# JY01.net
KiCad netlist of a schematic drawn in Altium Designer
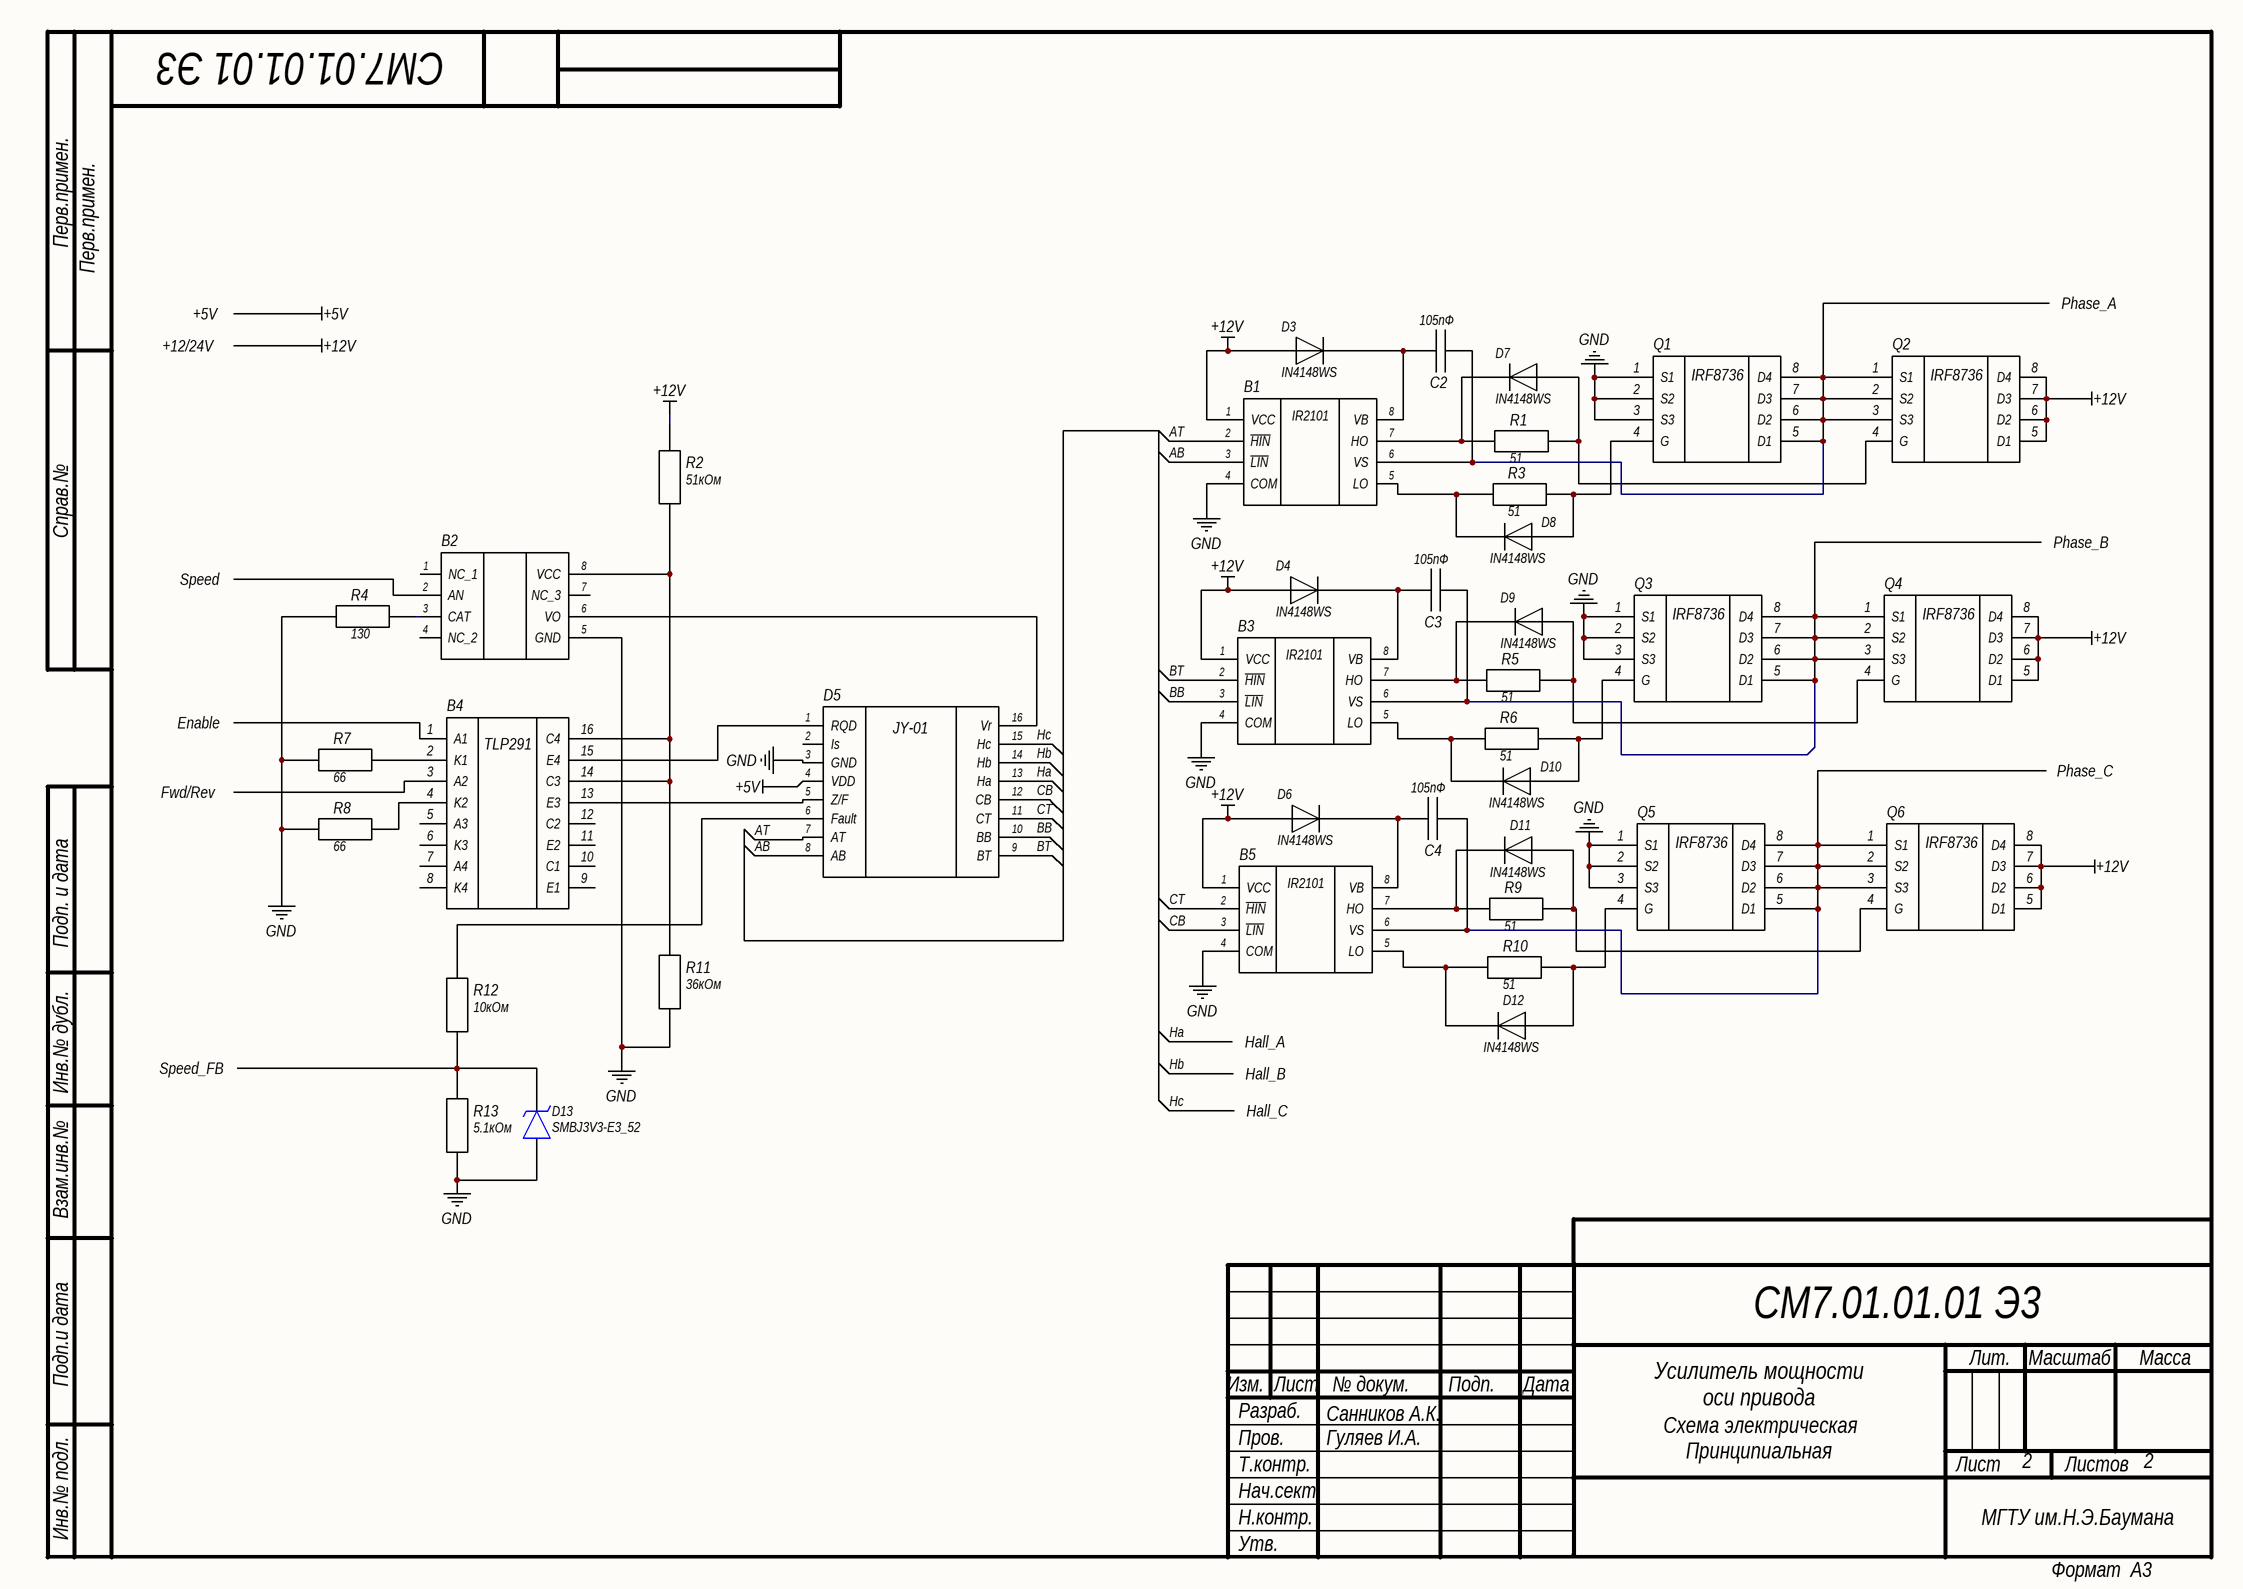
[diagram p0: Схема_принципиальная_JY01.SchDoc]

(export (version "E")
  (design (tool "Eeschema 10.0.6"))
  (components
    (comp (ref "B1")
      (value "IR2101S")
      (footprint "SOIC127P600X175-8N")
      (description "IC GATE DRVR HALF-BRIDGE 8SOIC")
      (libsource (lib "BLDC_Library") (part "IR2101S"))
    )
    (comp (ref "B2")
      (value "HCPL-4504-000E")
      (footprint "DIP762W65P254L965H470Q8N")
      (description "Optocoupler, Transistor Output, 1 Channel, DIP, 8 Pins, 25 mA, 3.75 kV, 25 %")
      (fields (field (name "MOUSER PART NUMBER") "630-HCPL-4504-000E"))
      (libsource (lib "BLDC_Library") (part "HCPL-4504-000E"))
    )
    (comp (ref "B3")
      (value "IR2101S")
      (footprint "SOIC127P600X175-8N")
      (description "IC GATE DRVR HALF-BRIDGE 8SOIC")
      (libsource (lib "BLDC_Library") (part "IR2101S"))
    )
    (comp (ref "B4")
      (value "TLP291-4_GB_E_T")
      (footprint "SOIC127P700X220-16N")
      (description "Photocoupler, Tr, 2.3mm, DC, SO16")
      (fields (field (name "MANUFACTURER_PART_NUMBER") "TLP291-4(GB,E(T"))
      (libsource (lib "BLDC_Library") (part "TLP291-4_GB_E_T"))
    )
    (comp (ref "B5")
      (value "IR2101S")
      (footprint "SOIC127P600X175-8N")
      (description "IC GATE DRVR HALF-BRIDGE 8SOIC")
      (libsource (lib "BLDC_Library") (part "IR2101S"))
    )
    (comp (ref "C2")
      (value "105пФ")
      (footprint "CAPC1608X87N")
      (description "C 0603")
      (fields (field (name "MANUFACTURER_PART_NUMBER") "C0603C222K4REC7411"))
      (libsource (lib "BLDC_Library") (part "C0603"))
    )
    (comp (ref "C3")
      (value "105пФ")
      (footprint "CAPC1608X87N")
      (description "C 0603")
      (fields (field (name "MANUFACTURER_PART_NUMBER") "C0603C222K4REC7411"))
      (libsource (lib "BLDC_Library") (part "C0603"))
    )
    (comp (ref "C4")
      (value "105пФ")
      (footprint "CAPC1608X87N")
      (description "C 0603")
      (fields (field (name "MANUFACTURER_PART_NUMBER") "C0603C222K4REC7411"))
      (libsource (lib "BLDC_Library") (part "C0603"))
    )
    (comp (ref "D3")
      (value "IN4148WS")
      (footprint "SOD2713X115N")
      (description "Small Signal Fast Switching Diode")
      (libsource (lib "BLDC_Library") (part "IN4148WS"))
    )
    (comp (ref "D4")
      (value "IN4148WS")
      (footprint "SOD2713X115N")
      (description "Small Signal Fast Switching Diode")
      (libsource (lib "BLDC_Library") (part "IN4148WS"))
    )
    (comp (ref "D5")
      (value "JY01-SOP16")
      (footprint "SOIC127P600X175-16N")
      (description "BLDC FOC Controller")
      (libsource (lib "BLDC_Library") (part "JY01-SOP16"))
    )
    (comp (ref "D6")
      (value "IN4148WS")
      (footprint "SOD2713X115N")
      (description "Small Signal Fast Switching Diode")
      (libsource (lib "BLDC_Library") (part "IN4148WS"))
    )
    (comp (ref "D7")
      (value "IN4148WS")
      (footprint "SOD2713X115N")
      (description "Small Signal Fast Switching Diode")
      (libsource (lib "BLDC_Library") (part "IN4148WS"))
    )
    (comp (ref "D8")
      (value "IN4148WS")
      (footprint "SOD2713X115N")
      (description "Small Signal Fast Switching Diode")
      (libsource (lib "BLDC_Library") (part "IN4148WS"))
    )
    (comp (ref "D9")
      (value "IN4148WS")
      (footprint "SOD2713X115N")
      (description "Small Signal Fast Switching Diode")
      (libsource (lib "BLDC_Library") (part "IN4148WS"))
    )
    (comp (ref "D10")
      (value "IN4148WS")
      (footprint "SOD2713X115N")
      (description "Small Signal Fast Switching Diode")
      (libsource (lib "BLDC_Library") (part "IN4148WS"))
    )
    (comp (ref "D11")
      (value "IN4148WS")
      (footprint "SOD2713X115N")
      (description "Small Signal Fast Switching Diode")
      (libsource (lib "BLDC_Library") (part "IN4148WS"))
    )
    (comp (ref "D12")
      (value "IN4148WS")
      (footprint "SOD2713X115N")
      (description "Small Signal Fast Switching Diode")
      (libsource (lib "BLDC_Library") (part "IN4148WS"))
    )
    (comp (ref "D13")
      (value "SMBJ3V3-E3_52")
      (footprint "SamacSys:DIOM5436X244N")
      (description "TVS Diode (Uni-directional)")
      (fields
        (field (name "MANUFACTURER_PART_NUMBER") "SMBJ3V3-E3/52")
        (field (name "MOUSER PART NUMBER") "625-SMBJ3V3-E3")
      )
      (libsource (lib "*") (part "SMBJ3V3-E3_52"))
    )
    (comp (ref "Q1")
      (value "IRF8736PBF")
      (footprint "SOIC127P600X175-8N")
      (description "Infineon IRF8736PBF N-channel MOSFET, 18 A, 30 V HEXFET, 8-Pin SOIC")
      (fields (field (name "MOUSER PART NUMBER") "942-IRF8736PBF"))
      (libsource (lib "BLDC_Library") (part "IRF8736PBF"))
    )
    (comp (ref "Q2")
      (value "IRF8736PBF")
      (footprint "SOIC127P600X175-8N")
      (description "Infineon IRF8736PBF N-channel MOSFET, 18 A, 30 V HEXFET, 8-Pin SOIC")
      (fields (field (name "MOUSER PART NUMBER") "942-IRF8736PBF"))
      (libsource (lib "BLDC_Library") (part "IRF8736PBF"))
    )
    (comp (ref "Q3")
      (value "IRF8736PBF")
      (footprint "SOIC127P600X175-8N")
      (description "Infineon IRF8736PBF N-channel MOSFET, 18 A, 30 V HEXFET, 8-Pin SOIC")
      (fields (field (name "MOUSER PART NUMBER") "942-IRF8736PBF"))
      (libsource (lib "BLDC_Library") (part "IRF8736PBF"))
    )
    (comp (ref "Q4")
      (value "IRF8736PBF")
      (footprint "SOIC127P600X175-8N")
      (description "Infineon IRF8736PBF N-channel MOSFET, 18 A, 30 V HEXFET, 8-Pin SOIC")
      (fields (field (name "MOUSER PART NUMBER") "942-IRF8736PBF"))
      (libsource (lib "BLDC_Library") (part "IRF8736PBF"))
    )
    (comp (ref "Q5")
      (value "IRF8736PBF")
      (footprint "SOIC127P600X175-8N")
      (description "Infineon IRF8736PBF N-channel MOSFET, 18 A, 30 V HEXFET, 8-Pin SOIC")
      (fields (field (name "MOUSER PART NUMBER") "942-IRF8736PBF"))
      (libsource (lib "BLDC_Library") (part "IRF8736PBF"))
    )
    (comp (ref "Q6")
      (value "IRF8736PBF")
      (footprint "SOIC127P600X175-8N")
      (description "Infineon IRF8736PBF N-channel MOSFET, 18 A, 30 V HEXFET, 8-Pin SOIC")
      (fields (field (name "MOUSER PART NUMBER") "942-IRF8736PBF"))
      (libsource (lib "BLDC_Library") (part "IRF8736PBF"))
    )
    (comp (ref "R1")
      (value "51")
      (footprint "RESC1608X55N")
      (description "Resistor 0603 Case 150 +/-0.1% 0.063W +/-25ppm/C")
      (fields (field (name "MANUFACTURER_PART_NUMBER") "CPF0603B150RE"))
      (libsource (lib "") (part "R0603_1"))
    )
    (comp (ref "R2")
      (value "51кОм")
      (footprint "RESC1608X55N")
      (description "Resistor 0603 Case 150 +/-0.1% 0.063W +/-25ppm/C")
      (fields (field (name "MANUFACTURER_PART_NUMBER") "CPF0603B150RE"))
      (libsource (lib "BLDC_Library") (part "R0603"))
    )
    (comp (ref "R3")
      (value "51")
      (footprint "RESC1608X55N")
      (description "Resistor 0603 Case 150 +/-0.1% 0.063W +/-25ppm/C")
      (fields (field (name "MANUFACTURER_PART_NUMBER") "CPF0603B150RE"))
      (libsource (lib "") (part "R0603_1"))
    )
    (comp (ref "R4")
      (value "130")
      (footprint "RESC1608X55N")
      (description "Resistor 0603 Case 150 +/-0.1% 0.063W +/-25ppm/C")
      (fields (field (name "MANUFACTURER_PART_NUMBER") "CPF0603B150RE"))
      (libsource (lib "") (part "R0603_1"))
    )
    (comp (ref "R5")
      (value "51")
      (footprint "RESC1608X55N")
      (description "Resistor 0603 Case 150 +/-0.1% 0.063W +/-25ppm/C")
      (fields (field (name "MANUFACTURER_PART_NUMBER") "CPF0603B150RE"))
      (libsource (lib "") (part "R0603_1"))
    )
    (comp (ref "R6")
      (value "51")
      (footprint "RESC1608X55N")
      (description "Resistor 0603 Case 150 +/-0.1% 0.063W +/-25ppm/C")
      (fields (field (name "MANUFACTURER_PART_NUMBER") "CPF0603B150RE"))
      (libsource (lib "") (part "R0603_1"))
    )
    (comp (ref "R7")
      (value "66")
      (footprint "RESC1608X55N")
      (description "Resistor 0603 Case 150 +/-0.1% 0.063W +/-25ppm/C")
      (fields (field (name "MANUFACTURER_PART_NUMBER") "CPF0603B150RE"))
      (libsource (lib "") (part "R0603_1"))
    )
    (comp (ref "R8")
      (value "66")
      (footprint "RESC1608X55N")
      (description "Resistor 0603 Case 150 +/-0.1% 0.063W +/-25ppm/C")
      (fields (field (name "MANUFACTURER_PART_NUMBER") "CPF0603B150RE"))
      (libsource (lib "") (part "R0603_1"))
    )
    (comp (ref "R9")
      (value "51")
      (footprint "RESC1608X55N")
      (description "Resistor 0603 Case 150 +/-0.1% 0.063W +/-25ppm/C")
      (fields (field (name "MANUFACTURER_PART_NUMBER") "CPF0603B150RE"))
      (libsource (lib "") (part "R0603_1"))
    )
    (comp (ref "R10")
      (value "51")
      (footprint "RESC1608X55N")
      (description "Resistor 0603 Case 150 +/-0.1% 0.063W +/-25ppm/C")
      (fields (field (name "MANUFACTURER_PART_NUMBER") "CPF0603B150RE"))
      (libsource (lib "") (part "R0603_1"))
    )
    (comp (ref "R11")
      (value "36кОм")
      (footprint "RESC1608X55N")
      (description "Resistor 0603 Case 150 +/-0.1% 0.063W +/-25ppm/C")
      (fields (field (name "MANUFACTURER_PART_NUMBER") "CPF0603B150RE"))
      (libsource (lib "BLDC_Library") (part "R0603"))
    )
    (comp (ref "R12")
      (value "10кОм")
      (footprint "RESC1608X55N")
      (description "Resistor 0603 Case 150 +/-0.1% 0.063W +/-25ppm/C")
      (fields (field (name "MANUFACTURER_PART_NUMBER") "CPF0603B150RE"))
      (libsource (lib "BLDC_Library") (part "R0603"))
    )
    (comp (ref "R13")
      (value "5.1кОм")
      (footprint "RESC1608X55N")
      (description "Resistor 0603 Case 150 +/-0.1% 0.063W +/-25ppm/C")
      (fields (field (name "MANUFACTURER_PART_NUMBER") "CPF0603B150RE"))
      (libsource (lib "BLDC_Library") (part "R0603"))
    )
  )
  (nets
    (net (code "1") (name "+5V") (class "Default")
      (node (ref "D5") (pin "4") (pinfunction "VDD_4") (pintype "passive"))
    )
    (net (code "2") (name "+12V") (class "Default")
      (node (ref "B1") (pin "1") (pinfunction "VCC_1") (pintype "passive"))
      (node (ref "B3") (pin "1") (pinfunction "VCC_1") (pintype "passive"))
      (node (ref "B5") (pin "1") (pinfunction "VCC_1") (pintype "passive"))
      (node (ref "D3") (pin "2") (pinfunction "A_2") (pintype "passive"))
      (node (ref "D4") (pin "2") (pinfunction "A_2") (pintype "passive"))
      (node (ref "D6") (pin "2") (pinfunction "A_2") (pintype "passive"))
      (node (ref "Q2") (pin "5") (pinfunction "D1_5") (pintype "passive"))
      (node (ref "Q2") (pin "6") (pinfunction "D2_6") (pintype "passive"))
      (node (ref "Q2") (pin "7") (pinfunction "D3_7") (pintype "passive"))
      (node (ref "Q2") (pin "8") (pinfunction "D4_8") (pintype "passive"))
      (node (ref "Q4") (pin "5") (pinfunction "D1_5") (pintype "passive"))
      (node (ref "Q4") (pin "6") (pinfunction "D2_6") (pintype "passive"))
      (node (ref "Q4") (pin "7") (pinfunction "D3_7") (pintype "passive"))
      (node (ref "Q4") (pin "8") (pinfunction "D4_8") (pintype "passive"))
      (node (ref "Q6") (pin "5") (pinfunction "D1_5") (pintype "passive"))
      (node (ref "Q6") (pin "6") (pinfunction "D2_6") (pintype "passive"))
      (node (ref "Q6") (pin "7") (pinfunction "D3_7") (pintype "passive"))
      (node (ref "Q6") (pin "8") (pinfunction "D4_8") (pintype "passive"))
      (node (ref "R2") (pin "2") (pinfunction "2_2") (pintype "passive"))
    )
    (net (code "3") (name "/AB") (class "Default")
      (node (ref "B1") (pin "3") (pinfunction "~{LIN}_3") (pintype "passive"))
      (node (ref "D5") (pin "8") (pinfunction "AB_8") (pintype "passive"))
    )
    (net (code "4") (name "/AT") (class "Default")
      (node (ref "B1") (pin "2") (pinfunction "~{HIN}_2") (pintype "passive"))
      (node (ref "D5") (pin "7") (pinfunction "AT_7") (pintype "passive"))
    )
    (net (code "5") (name "/BB") (class "Default")
      (node (ref "B3") (pin "3") (pinfunction "~{LIN}_3") (pintype "passive"))
      (node (ref "D5") (pin "10") (pinfunction "BB_10") (pintype "passive"))
    )
    (net (code "6") (name "/BT") (class "Default")
      (node (ref "B3") (pin "2") (pinfunction "~{HIN}_2") (pintype "passive"))
      (node (ref "D5") (pin "9") (pinfunction "BT_9") (pintype "passive"))
    )
    (net (code "7") (name "/CB") (class "Default")
      (node (ref "B5") (pin "3") (pinfunction "~{LIN}_3") (pintype "passive"))
      (node (ref "D5") (pin "12") (pinfunction "CB_12") (pintype "passive"))
    )
    (net (code "8") (name "/CT") (class "Default")
      (node (ref "B5") (pin "2") (pinfunction "~{HIN}_2") (pintype "passive"))
      (node (ref "D5") (pin "11") (pinfunction "CT_11") (pintype "passive"))
    )
    (net (code "9") (name "/Enable") (class "Default")
      (node (ref "B4") (pin "1") (pinfunction "A1_1") (pintype "passive"))
    )
    (net (code "10") (name "/Fwd{slash}Rev") (class "Default")
      (node (ref "B4") (pin "3") (pinfunction "A2_3") (pintype "passive"))
    )
    (net (code "11") (name "/Ha") (class "Default")
      (node (ref "D5") (pin "13") (pinfunction "Ha_13") (pintype "passive"))
    )
    (net (code "12") (name "/Hb") (class "Default")
      (node (ref "D5") (pin "14") (pinfunction "Hb_14") (pintype "passive"))
    )
    (net (code "13") (name "/Hc") (class "Default")
      (node (ref "D5") (pin "15") (pinfunction "Hc_15") (pintype "passive"))
    )
    (net (code "14") (name "/Phase_A") (class "Default")
      (node (ref "B1") (pin "6") (pinfunction "VS_6") (pintype "passive"))
      (node (ref "C2") (pin "1") (pinfunction "1_1") (pintype "passive"))
      (node (ref "Q1") (pin "5") (pinfunction "D1_5") (pintype "passive"))
      (node (ref "Q1") (pin "6") (pinfunction "D2_6") (pintype "passive"))
      (node (ref "Q1") (pin "7") (pinfunction "D3_7") (pintype "passive"))
      (node (ref "Q1") (pin "8") (pinfunction "D4_8") (pintype "passive"))
      (node (ref "Q2") (pin "1") (pinfunction "S1_1") (pintype "passive"))
      (node (ref "Q2") (pin "2") (pinfunction "S2_2") (pintype "passive"))
      (node (ref "Q2") (pin "3") (pinfunction "S3_3") (pintype "passive"))
    )
    (net (code "15") (name "/Phase_B") (class "Default")
      (node (ref "B3") (pin "6") (pinfunction "VS_6") (pintype "passive"))
      (node (ref "C3") (pin "1") (pinfunction "1_1") (pintype "passive"))
      (node (ref "Q3") (pin "5") (pinfunction "D1_5") (pintype "passive"))
      (node (ref "Q3") (pin "6") (pinfunction "D2_6") (pintype "passive"))
      (node (ref "Q3") (pin "7") (pinfunction "D3_7") (pintype "passive"))
      (node (ref "Q3") (pin "8") (pinfunction "D4_8") (pintype "passive"))
      (node (ref "Q4") (pin "1") (pinfunction "S1_1") (pintype "passive"))
      (node (ref "Q4") (pin "2") (pinfunction "S2_2") (pintype "passive"))
      (node (ref "Q4") (pin "3") (pinfunction "S3_3") (pintype "passive"))
    )
    (net (code "16") (name "/Phase_C") (class "Default")
      (node (ref "B5") (pin "6") (pinfunction "VS_6") (pintype "passive"))
      (node (ref "C4") (pin "1") (pinfunction "1_1") (pintype "passive"))
      (node (ref "Q5") (pin "5") (pinfunction "D1_5") (pintype "passive"))
      (node (ref "Q5") (pin "6") (pinfunction "D2_6") (pintype "passive"))
      (node (ref "Q5") (pin "7") (pinfunction "D3_7") (pintype "passive"))
      (node (ref "Q5") (pin "8") (pinfunction "D4_8") (pintype "passive"))
      (node (ref "Q6") (pin "1") (pinfunction "S1_1") (pintype "passive"))
      (node (ref "Q6") (pin "2") (pinfunction "S2_2") (pintype "passive"))
      (node (ref "Q6") (pin "3") (pinfunction "S3_3") (pintype "passive"))
    )
    (net (code "17") (name "/Speed") (class "Default")
      (node (ref "B2") (pin "2") (pinfunction "AN_2") (pintype "passive"))
    )
    (net (code "18") (name "/Speed_FB") (class "Default")
      (node (ref "D13") (pin "1") (pinfunction "K_1") (pintype "passive"))
      (node (ref "R12") (pin "1") (pinfunction "1_1") (pintype "passive"))
      (node (ref "R13") (pin "2") (pinfunction "2_2") (pintype "passive"))
    )
    (net (code "19") (name "GND") (class "Default")
      (node (ref "B1") (pin "4") (pinfunction "COM_4") (pintype "passive"))
      (node (ref "B2") (pin "5") (pinfunction "GND_5") (pintype "passive"))
      (node (ref "B3") (pin "4") (pinfunction "COM_4") (pintype "passive"))
      (node (ref "B5") (pin "4") (pinfunction "COM_4") (pintype "passive"))
      (node (ref "D13") (pin "2") (pinfunction "A_2") (pintype "passive"))
      (node (ref "D5") (pin "3") (pinfunction "GND_3") (pintype "passive"))
      (node (ref "Q1") (pin "1") (pinfunction "S1_1") (pintype "passive"))
      (node (ref "Q1") (pin "2") (pinfunction "S2_2") (pintype "passive"))
      (node (ref "Q1") (pin "3") (pinfunction "S3_3") (pintype "passive"))
      (node (ref "Q3") (pin "1") (pinfunction "S1_1") (pintype "passive"))
      (node (ref "Q3") (pin "2") (pinfunction "S2_2") (pintype "passive"))
      (node (ref "Q3") (pin "3") (pinfunction "S3_3") (pintype "passive"))
      (node (ref "Q5") (pin "1") (pinfunction "S1_1") (pintype "passive"))
      (node (ref "Q5") (pin "2") (pinfunction "S2_2") (pintype "passive"))
      (node (ref "Q5") (pin "3") (pinfunction "S3_3") (pintype "passive"))
      (node (ref "R11") (pin "1") (pinfunction "1_1") (pintype "passive"))
      (node (ref "R13") (pin "1") (pinfunction "1_1") (pintype "passive"))
      (node (ref "R4") (pin "1") (pinfunction "1_1") (pintype "passive"))
      (node (ref "R7") (pin "1") (pinfunction "1_1") (pintype "passive"))
      (node (ref "R8") (pin "1") (pinfunction "1_1") (pintype "passive"))
    )
    (net (code "20") (name "Net-(B1-HO)") (class "Default")
      (node (ref "B1") (pin "7") (pinfunction "HO_7") (pintype "passive"))
      (node (ref "D7") (pin "1") (pinfunction "K_1") (pintype "passive"))
      (node (ref "R1") (pin "1") (pinfunction "1_1") (pintype "passive"))
    )
    (net (code "21") (name "Net-(B1-LO)") (class "Default")
      (node (ref "B1") (pin "5") (pinfunction "LO_5") (pintype "passive"))
      (node (ref "D8") (pin "1") (pinfunction "K_1") (pintype "passive"))
      (node (ref "R3") (pin "1") (pinfunction "1_1") (pintype "passive"))
    )
    (net (code "22") (name "Net-(B1-VB)") (class "Default")
      (node (ref "B1") (pin "8") (pinfunction "VB_8") (pintype "passive"))
      (node (ref "C2") (pin "2") (pinfunction "2_2") (pintype "passive"))
      (node (ref "D3") (pin "1") (pinfunction "K_1") (pintype "passive"))
    )
    (net (code "23") (name "Net-(B2-CAT)") (class "Default")
      (node (ref "B2") (pin "3") (pinfunction "CAT_3") (pintype "passive"))
      (node (ref "R4") (pin "2") (pinfunction "2_2") (pintype "passive"))
    )
    (net (code "24") (name "Net-(B2-VCC)") (class "Default")
      (node (ref "B2") (pin "8") (pinfunction "VCC_8") (pintype "passive"))
      (node (ref "B4") (pin "14") (pinfunction "C3_14") (pintype "passive"))
      (node (ref "B4") (pin "16") (pinfunction "C4_16") (pintype "passive"))
      (node (ref "R11") (pin "2") (pinfunction "2_2") (pintype "passive"))
      (node (ref "R2") (pin "1") (pinfunction "1_1") (pintype "passive"))
    )
    (net (code "25") (name "Net-(B2-VO)") (class "Default")
      (node (ref "B2") (pin "6") (pinfunction "VO_6") (pintype "passive"))
      (node (ref "D5") (pin "16") (pinfunction "Vr_16") (pintype "passive"))
    )
    (net (code "26") (name "Net-(B3-HO)") (class "Default")
      (node (ref "B3") (pin "7") (pinfunction "HO_7") (pintype "passive"))
      (node (ref "D9") (pin "1") (pinfunction "K_1") (pintype "passive"))
      (node (ref "R5") (pin "1") (pinfunction "1_1") (pintype "passive"))
    )
    (net (code "27") (name "Net-(B3-LO)") (class "Default")
      (node (ref "B3") (pin "5") (pinfunction "LO_5") (pintype "passive"))
      (node (ref "D10") (pin "1") (pinfunction "K_1") (pintype "passive"))
      (node (ref "R6") (pin "1") (pinfunction "1_1") (pintype "passive"))
    )
    (net (code "28") (name "Net-(B3-VB)") (class "Default")
      (node (ref "B3") (pin "8") (pinfunction "VB_8") (pintype "passive"))
      (node (ref "C3") (pin "2") (pinfunction "2_2") (pintype "passive"))
      (node (ref "D4") (pin "1") (pinfunction "K_1") (pintype "passive"))
    )
    (net (code "29") (name "Net-(B4-E3)") (class "Default")
      (node (ref "B4") (pin "13") (pinfunction "E3_13") (pintype "passive"))
      (node (ref "D5") (pin "5") (pinfunction "Z/F_5") (pintype "passive"))
    )
    (net (code "30") (name "Net-(B4-E4)") (class "Default")
      (node (ref "B4") (pin "15") (pinfunction "E4_15") (pintype "passive"))
      (node (ref "D5") (pin "1") (pinfunction "RQD_1") (pintype "passive"))
    )
    (net (code "31") (name "Net-(B4-K1)") (class "Default")
      (node (ref "B4") (pin "2") (pinfunction "K1_2") (pintype "passive"))
      (node (ref "R7") (pin "2") (pinfunction "2_2") (pintype "passive"))
    )
    (net (code "32") (name "Net-(B4-K2)") (class "Default")
      (node (ref "B4") (pin "4") (pinfunction "K2_4") (pintype "passive"))
      (node (ref "R8") (pin "2") (pinfunction "2_2") (pintype "passive"))
    )
    (net (code "33") (name "Net-(B5-HO)") (class "Default")
      (node (ref "B5") (pin "7") (pinfunction "HO_7") (pintype "passive"))
      (node (ref "D11") (pin "1") (pinfunction "K_1") (pintype "passive"))
      (node (ref "R9") (pin "1") (pinfunction "1_1") (pintype "passive"))
    )
    (net (code "34") (name "Net-(B5-LO)") (class "Default")
      (node (ref "B5") (pin "5") (pinfunction "LO_5") (pintype "passive"))
      (node (ref "D12") (pin "1") (pinfunction "K_1") (pintype "passive"))
      (node (ref "R10") (pin "1") (pinfunction "1_1") (pintype "passive"))
    )
    (net (code "35") (name "Net-(B5-VB)") (class "Default")
      (node (ref "B5") (pin "8") (pinfunction "VB_8") (pintype "passive"))
      (node (ref "C4") (pin "2") (pinfunction "2_2") (pintype "passive"))
      (node (ref "D6") (pin "1") (pinfunction "K_1") (pintype "passive"))
    )
    (net (code "36") (name "Net-(D5-Fault)") (class "Default")
      (node (ref "D5") (pin "6") (pinfunction "Fault_6") (pintype "passive"))
      (node (ref "R12") (pin "2") (pinfunction "2_2") (pintype "passive"))
    )
    (net (code "37") (name "Net-(D7-A)") (class "Default")
      (node (ref "D7") (pin "2") (pinfunction "A_2") (pintype "passive"))
      (node (ref "Q2") (pin "4") (pinfunction "G_4") (pintype "passive"))
      (node (ref "R1") (pin "2") (pinfunction "2_2") (pintype "passive"))
    )
    (net (code "38") (name "Net-(D8-A)") (class "Default")
      (node (ref "D8") (pin "2") (pinfunction "A_2") (pintype "passive"))
      (node (ref "Q1") (pin "4") (pinfunction "G_4") (pintype "passive"))
      (node (ref "R3") (pin "2") (pinfunction "2_2") (pintype "passive"))
    )
    (net (code "39") (name "Net-(D9-A)") (class "Default")
      (node (ref "D9") (pin "2") (pinfunction "A_2") (pintype "passive"))
      (node (ref "Q4") (pin "4") (pinfunction "G_4") (pintype "passive"))
      (node (ref "R5") (pin "2") (pinfunction "2_2") (pintype "passive"))
    )
    (net (code "40") (name "Net-(D10-A)") (class "Default")
      (node (ref "D10") (pin "2") (pinfunction "A_2") (pintype "passive"))
      (node (ref "Q3") (pin "4") (pinfunction "G_4") (pintype "passive"))
      (node (ref "R6") (pin "2") (pinfunction "2_2") (pintype "passive"))
    )
    (net (code "41") (name "Net-(D11-A)") (class "Default")
      (node (ref "D11") (pin "2") (pinfunction "A_2") (pintype "passive"))
      (node (ref "Q6") (pin "4") (pinfunction "G_4") (pintype "passive"))
      (node (ref "R9") (pin "2") (pinfunction "2_2") (pintype "passive"))
    )
    (net (code "42") (name "Net-(D12-A)") (class "Default")
      (node (ref "D12") (pin "2") (pinfunction "A_2") (pintype "passive"))
      (node (ref "Q5") (pin "4") (pinfunction "G_4") (pintype "passive"))
      (node (ref "R10") (pin "2") (pinfunction "2_2") (pintype "passive"))
    )
    (net (code "43") (name "unconnected-(B2-NC_1-Pad1)") (class "Default")
      (node (ref "B2") (pin "1") (pinfunction "NC_1_1") (pintype "passive"))
    )
    (net (code "44") (name "unconnected-(B2-NC_2-Pad4)") (class "Default")
      (node (ref "B2") (pin "4") (pinfunction "NC_2_4") (pintype "passive"))
    )
    (net (code "45") (name "unconnected-(B2-NC_3-Pad7)") (class "Default")
      (node (ref "B2") (pin "7") (pinfunction "NC_3_7") (pintype "passive"))
    )
    (net (code "46") (name "unconnected-(B4-A3-Pad5)") (class "Default")
      (node (ref "B4") (pin "5") (pinfunction "A3_5") (pintype "passive"))
    )
    (net (code "47") (name "unconnected-(B4-A4-Pad7)") (class "Default")
      (node (ref "B4") (pin "7") (pinfunction "A4_7") (pintype "passive"))
    )
    (net (code "48") (name "unconnected-(B4-C1-Pad10)") (class "Default")
      (node (ref "B4") (pin "10") (pinfunction "C1_10") (pintype "passive"))
    )
    (net (code "49") (name "unconnected-(B4-C2-Pad12)") (class "Default")
      (node (ref "B4") (pin "12") (pinfunction "C2_12") (pintype "passive"))
    )
    (net (code "50") (name "unconnected-(B4-E1-Pad9)") (class "Default")
      (node (ref "B4") (pin "9") (pinfunction "E1_9") (pintype "passive"))
    )
    (net (code "51") (name "unconnected-(B4-E2-Pad11)") (class "Default")
      (node (ref "B4") (pin "11") (pinfunction "E2_11") (pintype "passive"))
    )
    (net (code "52") (name "unconnected-(B4-K3-Pad6)") (class "Default")
      (node (ref "B4") (pin "6") (pinfunction "K3_6") (pintype "passive"))
    )
    (net (code "53") (name "unconnected-(B4-K4-Pad8)") (class "Default")
      (node (ref "B4") (pin "8") (pinfunction "K4_8") (pintype "passive"))
    )
    (net (code "54") (name "unconnected-(D5-Is-Pad2)") (class "Default")
      (node (ref "D5") (pin "2") (pinfunction "Is_2") (pintype "passive"))
    )
  )
)
